# PowerSupply.net
KiCad netlist of a schematic drawn in Altium Designer
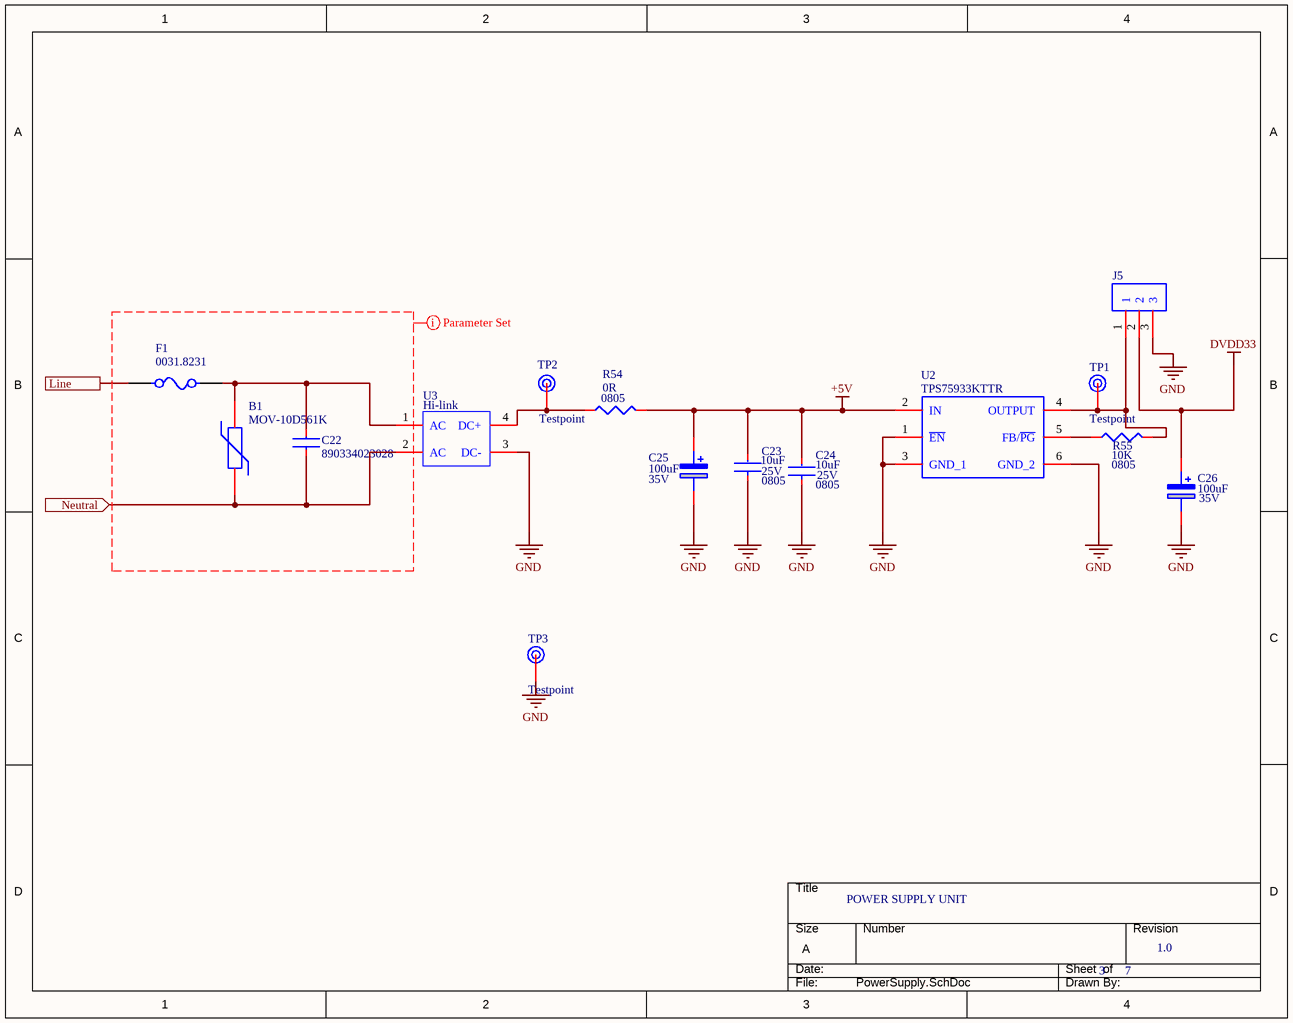
[diagram p0: PowerSupply.SchDoc]

(export (version "E")
  (design (tool "Eeschema 10.0.6"))
  (components
    (comp (ref "B1")
      (value "MOV-10D561K")
      (footprint "MOV10D561K")
      (description "Varistors 180pF 560volts 10%")
      (fields (field (name "MOUSER PART NUMBER") "652-MOV-10D561K"))
      (libsource (lib "MOV-10D561K") (part "MOV-10D561K"))
    )
    (comp (ref "C22")
      (value "890334023028")
      (footprint "890334023028")
      (fields (field (name "MOUSER PART NUMBER") "710-890334023028"))
      (libsource (lib "890334023028") (part "890334023028"))
    )
    (comp (ref "C23")
      (value "GRM21BC71E106KE01L")
      (footprint "FP-GRM21B-0_2-e0_2_0_7-IPC_B")
      (fields (field (name "CAPACITANCE") "10uF") (field (name "VOLTAGE") "25V") (field (name "SIZE") "0805"))
      (libsource (lib "Altium Content Vault") (part "b4654b650e69147ec39a6b967a45e02"))
    )
    (comp (ref "C24")
      (value "GRM21BC71E106KE01L")
      (footprint "FP-GRM21B-0_2-e0_2_0_7-IPC_B")
      (fields (field (name "CAPACITANCE") "10uF") (field (name "VOLTAGE") "25V") (field (name "SIZE") "0805"))
      (libsource (lib "Altium Content Vault") (part "b4654b650e69147ec39a6b967a45e02"))
    )
    (comp (ref "C25")
      (value "ESC107M035AE3AA")
      (footprint "CAPPRD250W50D630H1250")
      (fields
        (field (name "MOUSER PART NUMBER") "80-ESC107M035AE3AA")
        (field (name "CAPACITANCE") "100uF")
        (field (name "VOLTAGE") "35V")
      )
      (libsource (lib "ESC107M035AE3AA") (part "ESC107M035AE3AA"))
    )
    (comp (ref "C26")
      (value "ESC107M035AE3AA")
      (footprint "CAPPRD250W50D630H1250")
      (fields
        (field (name "MOUSER PART NUMBER") "80-ESC107M035AE3AA")
        (field (name "CAPACITANCE") "100uF")
        (field (name "VOLTAGE") "35V")
      )
      (libsource (lib "ESC107M035AE3AA") (part "ESC107M035AE3AA"))
    )
    (comp (ref "F1")
      (value "0031.8231")
      (footprint "FP-0031_8231-MFG")
      (description "FUSE BLOK CARTRIDGE 600V 16A PCB")
      (fields
        (field (name "OCTOPART") "https://octopart.com/0031.8231-schurter-8659")
        (field (name "MANUFACTURER") "Schurter")
      )
      (libsource (lib "Altium Content Vault") (part "5bcf9b9f640e542cf0359d10258e979"))
    )
    (comp (ref "J5")
      (value "HTSW-103-07-G-S")
      (footprint "HDRV3W64P0X254_1X3_749X249X858P")
      (description "Samtec HTSW, 2.54mm Pitch, 3 Way, 1 Row, Vertical Pin Header, Through Hole")
      (fields (field (name "MOUSER PART NUMBER") "200-HTSW10307GS"))
      (libsource (lib "HTSW-103-07-G-S") (part "HTSW-103-07-G-S"))
    )
    (comp (ref "R54")
      (value "WSL080500000ZEA9")
      (footprint "RESC2013X84N")
      (fields
        (field (name "MOUSER PART NUMBER") "71-WSL080500000ZEA9")
        (field (name "RESISTANCE") "0R")
        (field (name "SIZE") "0805")
      )
      (libsource (lib "WSL080500000ZEA9") (part "WSL080500000ZEA9"))
    )
    (comp (ref "R55")
      (value "CRCW201010K0JNEFIF")
      (footprint "RESC2013X84N")
      (fields
        (field (name "MOUSER PART NUMBER") "71-WSL080500000ZEA9")
        (field (name "MANUFACTURER_PART_NUMBER") "WSL080500000ZEA9")
        (field (name "RESISTANCE") "10K")
        (field (name "SIZE") "0805")
      )
      (libsource (lib "WSL080500000ZEA9") (part "WSL080500000ZEA9"))
    )
    (comp (ref "TP1")
      (value "Testpoint")
      (footprint "Testpad")
      (libsource (lib "Schlib1") (part "Testpoint"))
    )
    (comp (ref "TP2")
      (value "Testpoint")
      (footprint "Testpad")
      (libsource (lib "Schlib1") (part "Testpoint"))
    )
    (comp (ref "TP3")
      (value "Testpoint")
      (footprint "Testpad")
      (libsource (lib "Schlib1") (part "Testpoint"))
    )
    (comp (ref "U2")
      (value "TPS75933KTTR")
      (footprint "TPS75933KTTR")
      (description "Fast-Transient Response, 7.5-A, Low-Dropout Voltage Regulators with Power Good")
      (fields (field (name "MOUSER PART NUMBER") "595-TPS75933KTTR"))
      (libsource (lib "TPS75933KTTR") (part "TPS75933KTTR"))
    )
    (comp (ref "U3")
      (value "Hi-link")
      (footprint "Hi-Link")
      (description "Hi-Link HLK-20M05 220VAC to 5VDC 20W Step-Down Power Supply Module")
      (libsource (lib "Schlib1") (part "Hi-link"))
    )
  )
  (nets
    (net (code "1") (name "+5V") (class "Default")
      (node (ref "C23") (pin "2") (pinfunction "2_2") (pintype "passive"))
      (node (ref "C24") (pin "2") (pinfunction "2_2") (pintype "passive"))
      (node (ref "C25") (pin "1") (pinfunction "+_1") (pintype "passive"))
      (node (ref "R54") (pin "1") (pinfunction "1_1") (pintype "passive"))
      (node (ref "U2") (pin "2") (pinfunction "IN_2") (pintype "passive"))
    )
    (net (code "2") (name "/Line") (class "Default")
      (node (ref "F1") (pin "1") (pinfunction "1_1") (pintype "passive"))
    )
    (net (code "3") (name "/Neutral") (class "Default")
      (node (ref "B1") (pin "1") (pinfunction "1_1") (pintype "passive"))
      (node (ref "C22") (pin "1") (pinfunction "1_1") (pintype "passive"))
      (node (ref "U3") (pin "2") (pinfunction "AC_2") (pintype "passive"))
    )
    (net (code "4") (name "DVDD33") (class "Default")
      (node (ref "C26") (pin "1") (pinfunction "+_1") (pintype "passive"))
      (node (ref "J5") (pin "2") (pinfunction "2_2") (pintype "passive"))
    )
    (net (code "5") (name "GND") (class "Default")
      (node (ref "C23") (pin "1") (pinfunction "1_1") (pintype "passive"))
      (node (ref "C24") (pin "1") (pinfunction "1_1") (pintype "passive"))
      (node (ref "C25") (pin "2") (pinfunction "-_2") (pintype "passive"))
      (node (ref "C26") (pin "2") (pinfunction "-_2") (pintype "passive"))
      (node (ref "J5") (pin "3") (pinfunction "3_3") (pintype "passive"))
      (node (ref "TP3") (pin "1") (pinfunction "1_1") (pintype "passive"))
      (node (ref "U2") (pin "1") (pinfunction "~{EN}_1") (pintype "passive"))
      (node (ref "U2") (pin "3") (pinfunction "GND_1_3") (pintype "passive"))
      (node (ref "U2") (pin "6") (pinfunction "GND_2_6") (pintype "passive"))
      (node (ref "U3") (pin "3") (pinfunction "DC-_3") (pintype "passive"))
    )
    (net (code "6") (name "Net-(B1-Pad2)") (class "Default")
      (node (ref "B1") (pin "2") (pinfunction "2_2") (pintype "passive"))
      (node (ref "C22") (pin "2") (pinfunction "2_2") (pintype "passive"))
      (node (ref "F1") (pin "2") (pinfunction "2_2") (pintype "passive"))
      (node (ref "U3") (pin "1") (pinfunction "AC_1") (pintype "passive"))
    )
    (net (code "7") (name "Net-(U2-FB{slash}~{PG})") (class "Default")
      (node (ref "R55") (pin "2") (pinfunction "2_2") (pintype "passive"))
      (node (ref "U2") (pin "5") (pinfunction "FB/~{PG}_5") (pintype "passive"))
    )
    (net (code "8") (name "Net-(U2-OUTPUT)") (class "Default")
      (node (ref "J5") (pin "1") (pinfunction "1_1") (pintype "passive"))
      (node (ref "R55") (pin "1") (pinfunction "1_1") (pintype "passive"))
      (node (ref "TP1") (pin "1") (pinfunction "1_1") (pintype "passive"))
      (node (ref "U2") (pin "4") (pinfunction "OUTPUT_4") (pintype "passive"))
    )
    (net (code "9") (name "Net-(U3-DC+)") (class "Default")
      (node (ref "R54") (pin "2") (pinfunction "2_2") (pintype "passive"))
      (node (ref "TP2") (pin "1") (pinfunction "1_1") (pintype "passive"))
      (node (ref "U3") (pin "4") (pinfunction "DC+_4") (pintype "passive"))
    )
  )
)
